# OSSILEDController2132.net
KiCad netlist of a schematic drawn in EAGLE
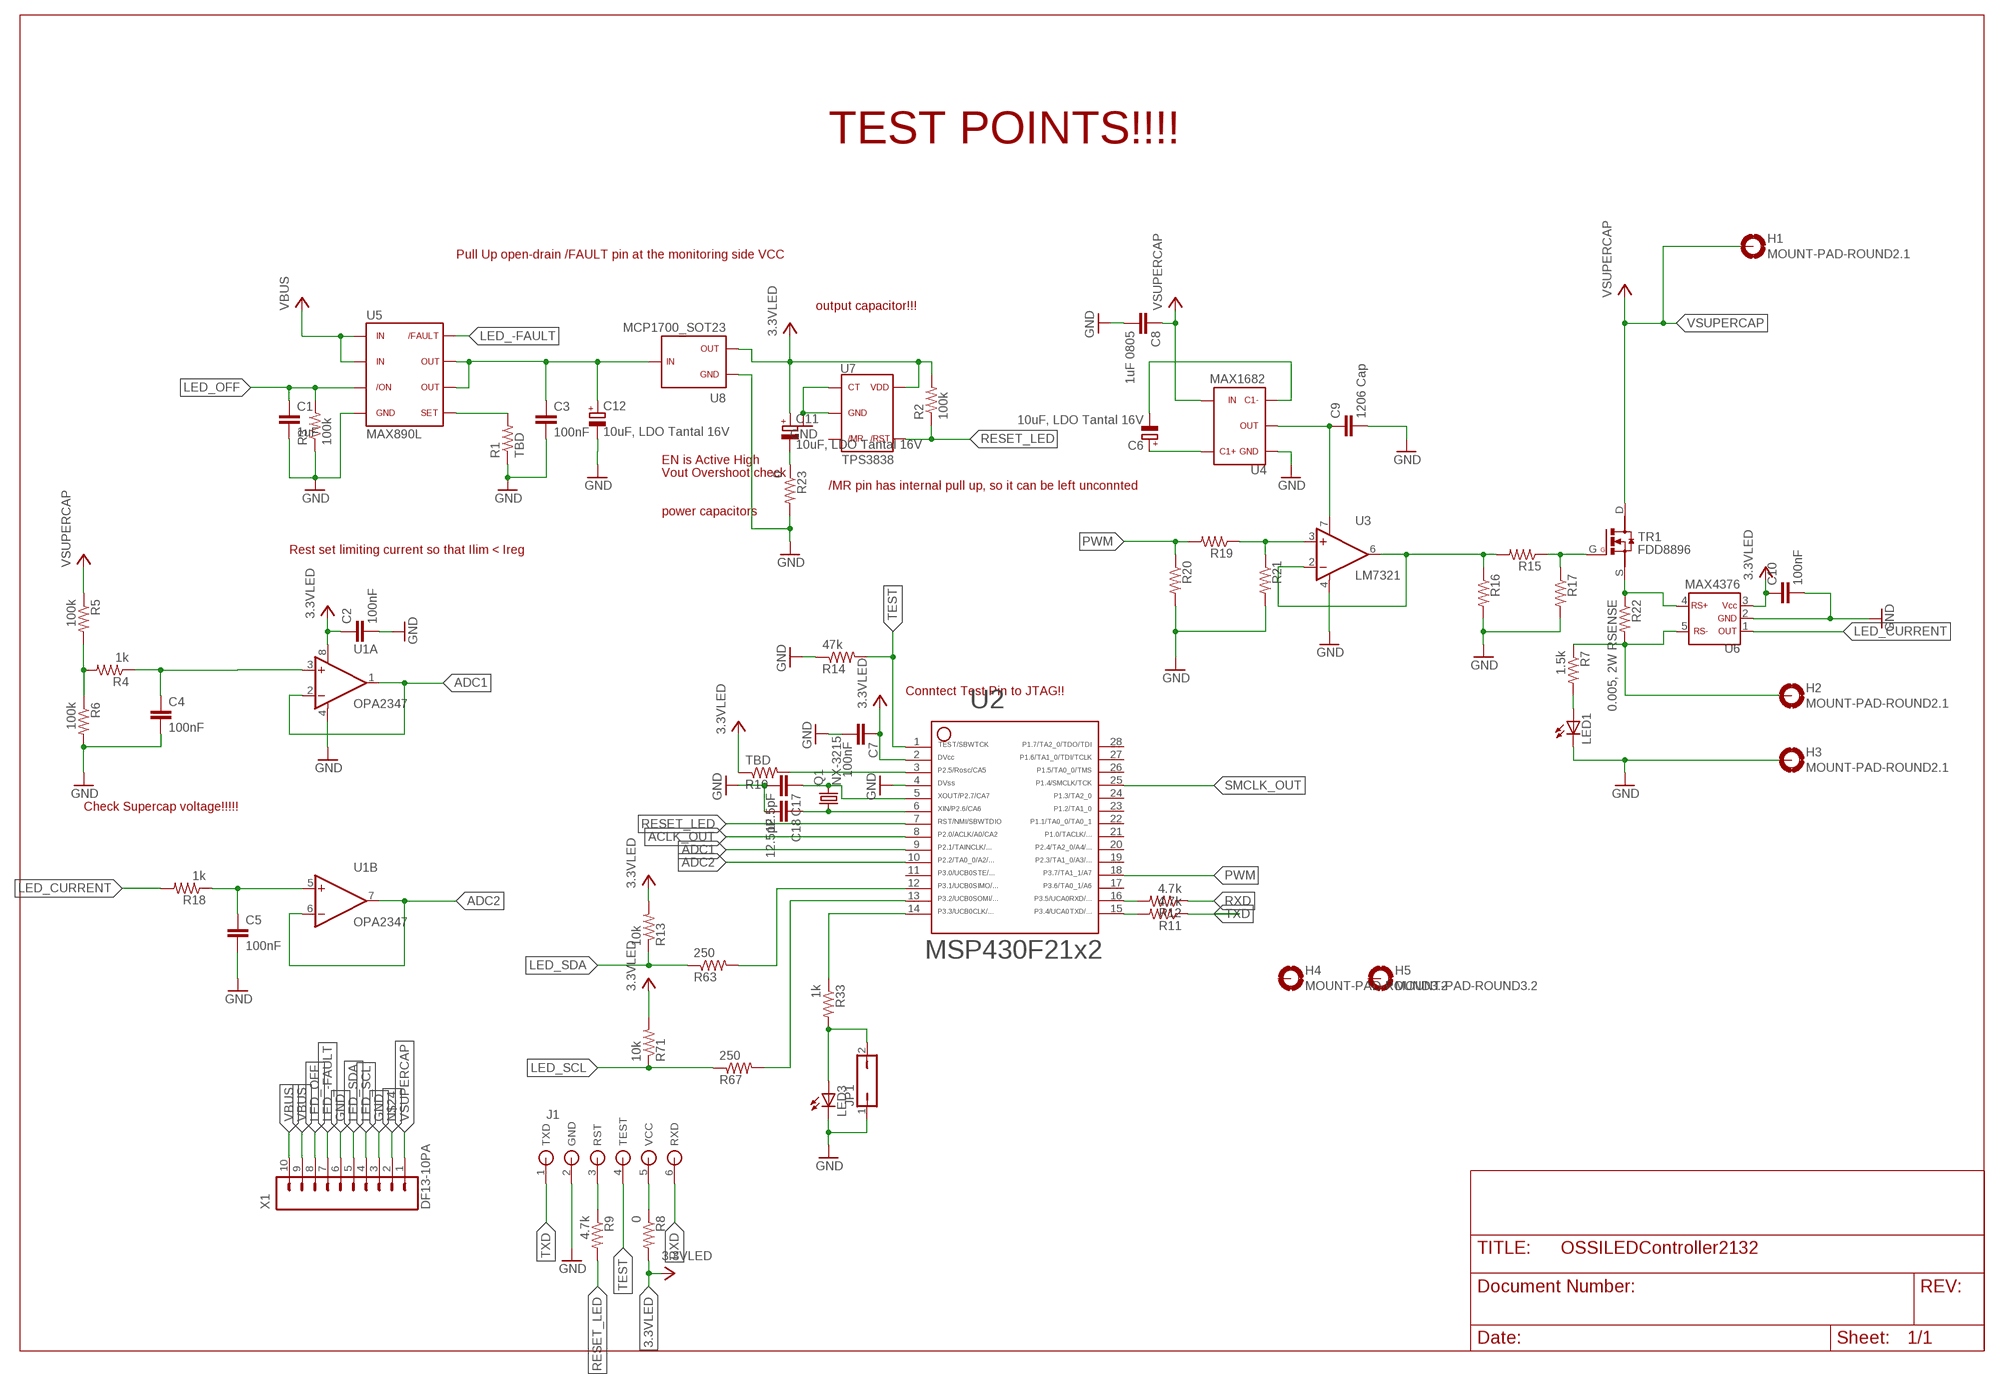
[diagram p0: schematic, sheet 1]

(export (version "E")
  (design (tool "Eeschema 10.0.6"))
  (components
    (comp (ref "C1")
      (value "1uF")
      (footprint "eagle-import:C0603(1608)")
      (libsource (lib "eagle-import") (part "C0603(1608)"))
    )
    (comp (ref "C2")
      (value "100nF")
      (footprint "eagle-import:C0603(1608)")
      (libsource (lib "eagle-import") (part "C0603(1608)"))
    )
    (comp (ref "C3")
      (value "100nF")
      (footprint "eagle-import:C0603(1608)")
      (libsource (lib "eagle-import") (part "C0603(1608)"))
    )
    (comp (ref "C4")
      (value "100nF")
      (footprint "eagle-import:C0603(1608)")
      (libsource (lib "eagle-import") (part "C0603(1608)"))
    )
    (comp (ref "C5")
      (value "100nF")
      (footprint "eagle-import:C0603(1608)")
      (libsource (lib "eagle-import") (part "C0603(1608)"))
    )
    (comp (ref "C6")
      (value "10uF, LDO Tantal 16V")
      (footprint "eagle-import:C1206(3216)-A")
      (libsource (lib "eagle-import") (part "C-TANTAL-A"))
    )
    (comp (ref "C7")
      (value "100nF")
      (footprint "eagle-import:C0603(1608)")
      (libsource (lib "eagle-import") (part "C0603(1608)"))
    )
    (comp (ref "C8")
      (value "1uF 0805")
      (footprint "eagle-import:C0805(2012)")
      (libsource (lib "eagle-import") (part "C0805(2012)"))
    )
    (comp (ref "C9")
      (value "1206 Cap")
      (footprint "eagle-import:C1206-GCM31")
      (libsource (lib "eagle-import") (part "C1206(3216)-GCM31"))
    )
    (comp (ref "C10")
      (value "100nF")
      (footprint "eagle-import:C0603(1608)")
      (libsource (lib "eagle-import") (part "C0603(1608)"))
    )
    (comp (ref "C11")
      (value "10uF, LDO Tantal 16V")
      (footprint "eagle-import:C1206(3216)-A")
      (libsource (lib "eagle-import") (part "C-TANTAL-A"))
    )
    (comp (ref "C12")
      (value "10uF, LDO Tantal 16V")
      (footprint "eagle-import:C1206(3216)-A")
      (libsource (lib "eagle-import") (part "C-TANTAL-A"))
    )
    (comp (ref "C17")
      (value "12.5pF")
      (footprint "eagle-import:C0603(1608)")
      (libsource (lib "eagle-import") (part "C0603(1608)"))
    )
    (comp (ref "C18")
      (value "12.5pF")
      (footprint "eagle-import:C0603(1608)")
      (libsource (lib "eagle-import") (part "C0603(1608)"))
    )
    (comp (ref "H1")
      (value "MOUNT-PAD-ROUND2.1")
      (footprint "eagle-import:2.1-PAD-ROUND")
      (libsource (lib "eagle-import") (part "MOUNT-PAD-ROUND2.1"))
    )
    (comp (ref "H2")
      (value "MOUNT-PAD-ROUND2.1")
      (footprint "eagle-import:2.1-PAD-ROUND")
      (libsource (lib "eagle-import") (part "MOUNT-PAD-ROUND2.1"))
    )
    (comp (ref "H3")
      (value "MOUNT-PAD-ROUND2.1")
      (footprint "eagle-import:2.1-PAD-ROUND")
      (libsource (lib "eagle-import") (part "MOUNT-PAD-ROUND2.1"))
    )
    (comp (ref "H4")
      (value "MOUNT-PAD-ROUND3.2")
      (footprint "eagle-import:3.2-PAD-ROUND")
      (libsource (lib "eagle-import") (part "MOUNT-PAD-ROUND3.2"))
    )
    (comp (ref "H5")
      (value "MOUNT-PAD-ROUND3.2")
      (footprint "eagle-import:3.2-PAD-ROUND")
      (libsource (lib "eagle-import") (part "MOUNT-PAD-ROUND3.2"))
    )
    (comp (ref "J1")
      (value "JTAG-SBW-6")
      (footprint "eagle-import:SMD-PAD-6")
      (libsource (lib "eagle-import") (part "JTAG-SBW-6"))
    )
    (comp (ref "JP1")
      (value "JP1Q")
      (footprint "eagle-import:JP1")
      (libsource (lib "eagle-import") (part "JP1Q"))
    )
    (comp (ref "LED1")
      (value "LEDCHIPLED_0603")
      (footprint "eagle-import:CHIPLED_0603")
      (libsource (lib "eagle-import") (part "LEDCHIPLED_0603"))
    )
    (comp (ref "LED3")
      (value "LED0603")
      (footprint "eagle-import:LED-0603")
      (libsource (lib "eagle-import") (part "LED0603"))
    )
    (comp (ref "Q1")
      (value "NX-3215")
      (footprint "eagle-import:NX-3215")
      (libsource (lib "eagle-import") (part "NX-3215"))
    )
    (comp (ref "R1")
      (value "TBD")
      (footprint "eagle-import:R0603(1608)")
      (libsource (lib "eagle-import") (part "R0603(1608)"))
    )
    (comp (ref "R2")
      (value "100k")
      (footprint "eagle-import:R0603(1608)")
      (libsource (lib "eagle-import") (part "R0603(1608)"))
    )
    (comp (ref "R3")
      (value "100k")
      (footprint "eagle-import:R0603(1608)")
      (libsource (lib "eagle-import") (part "R0603(1608)"))
    )
    (comp (ref "R4")
      (value "1k")
      (footprint "eagle-import:R0603(1608)")
      (libsource (lib "eagle-import") (part "R0603(1608)"))
    )
    (comp (ref "R5")
      (value "100k")
      (footprint "eagle-import:R0603(1608)")
      (libsource (lib "eagle-import") (part "R0603(1608)"))
    )
    (comp (ref "R6")
      (value "100k")
      (footprint "eagle-import:R0603(1608)")
      (libsource (lib "eagle-import") (part "R0603(1608)"))
    )
    (comp (ref "R7")
      (value "1.5k")
      (footprint "eagle-import:R0603(1608)")
      (libsource (lib "eagle-import") (part "R0603(1608)"))
    )
    (comp (ref "R8")
      (value "0")
      (footprint "eagle-import:R0603(1608)")
      (libsource (lib "eagle-import") (part "R0603(1608)"))
    )
    (comp (ref "R9")
      (value "4.7k")
      (footprint "eagle-import:R0603(1608)")
      (libsource (lib "eagle-import") (part "R0603(1608)"))
    )
    (comp (ref "R10")
      (value "TBD")
      (footprint "eagle-import:R0603(1608)")
      (libsource (lib "eagle-import") (part "R0603(1608)"))
    )
    (comp (ref "R11")
      (value "4.7k")
      (footprint "eagle-import:R0603(1608)")
      (libsource (lib "eagle-import") (part "R0603(1608)"))
    )
    (comp (ref "R12")
      (value "4.7k")
      (footprint "eagle-import:R0603(1608)")
      (libsource (lib "eagle-import") (part "R0603(1608)"))
    )
    (comp (ref "R13")
      (value "10k")
      (footprint "eagle-import:R0603(1608)")
      (libsource (lib "eagle-import") (part "R0603(1608)"))
    )
    (comp (ref "R14")
      (value "47k")
      (footprint "eagle-import:R0603(1608)")
      (libsource (lib "eagle-import") (part "R0603(1608)"))
    )
    (comp (ref "R15")
      (value "R0603(1608)")
      (footprint "eagle-import:R0603(1608)")
      (libsource (lib "eagle-import") (part "R0603(1608)"))
    )
    (comp (ref "R16")
      (value "R0603(1608)")
      (footprint "eagle-import:R0603(1608)")
      (libsource (lib "eagle-import") (part "R0603(1608)"))
    )
    (comp (ref "R17")
      (value "R0603(1608)")
      (footprint "eagle-import:R0603(1608)")
      (libsource (lib "eagle-import") (part "R0603(1608)"))
    )
    (comp (ref "R18")
      (value "1k")
      (footprint "eagle-import:R0603(1608)")
      (libsource (lib "eagle-import") (part "R0603(1608)"))
    )
    (comp (ref "R19")
      (value "R0603(1608)")
      (footprint "eagle-import:R0603(1608)")
      (libsource (lib "eagle-import") (part "R0603(1608)"))
    )
    (comp (ref "R20")
      (value "R0603(1608)")
      (footprint "eagle-import:R0603(1608)")
      (libsource (lib "eagle-import") (part "R0603(1608)"))
    )
    (comp (ref "R21")
      (value "R0603(1608)")
      (footprint "eagle-import:R0603(1608)")
      (libsource (lib "eagle-import") (part "R0603(1608)"))
    )
    (comp (ref "R22")
      (value "0.005, 2W RSENSE")
      (footprint "eagle-import:R4527(12070)")
      (libsource (lib "eagle-import") (part "RWSR2"))
    )
    (comp (ref "R23")
      (value "0")
      (footprint "eagle-import:R0603(1608)")
      (libsource (lib "eagle-import") (part "R0603(1608)"))
    )
    (comp (ref "R33")
      (value "1k")
      (footprint "eagle-import:R0603(1608)")
      (libsource (lib "eagle-import") (part "R0603(1608)"))
    )
    (comp (ref "R63")
      (value "250")
      (footprint "eagle-import:R0603(1608)")
      (libsource (lib "eagle-import") (part "R0603(1608)"))
    )
    (comp (ref "R67")
      (value "250")
      (footprint "eagle-import:R0603(1608)")
      (libsource (lib "eagle-import") (part "R0603(1608)"))
    )
    (comp (ref "R71")
      (value "10k")
      (footprint "eagle-import:R0603(1608)")
      (libsource (lib "eagle-import") (part "R0603(1608)"))
    )
    (comp (ref "TR1")
      (value "FDD8896")
      (footprint "eagle-import:TO252")
      (libsource (lib "eagle-import") (part "FDD8896"))
    )
    (comp (ref "U1")
      (value "OPA2347")
      (footprint "eagle-import:SOT23-8DCN")
      (libsource (lib "eagle-import") (part "OPA2347"))
    )
    (comp (ref "U2")
      (value "MSP430F2132")
      (footprint "eagle-import:PW28")
      (libsource (lib "eagle-import") (part "MSP430F2132"))
    )
    (comp (ref "U3")
      (value "LM7321")
      (footprint "eagle-import:SO8")
      (libsource (lib "eagle-import") (part "LM7321"))
    )
    (comp (ref "U4")
      (value "MAX1682")
      (footprint "eagle-import:SOT23-5DBV")
      (libsource (lib "eagle-import") (part "MAX1682"))
    )
    (comp (ref "U5")
      (value "MAX890L")
      (footprint "eagle-import:SO8")
      (libsource (lib "eagle-import") (part "MAX890L"))
    )
    (comp (ref "U6")
      (value "MAX4376")
      (footprint "eagle-import:SOT23-5DBV")
      (libsource (lib "eagle-import") (part "MAX4376"))
    )
    (comp (ref "U7")
      (value "TPS3838")
      (footprint "eagle-import:SOT23-5DBV")
      (libsource (lib "eagle-import") (part "TPS3838"))
    )
    (comp (ref "U8")
      (value "MCP1700_SOT23")
      (footprint "eagle-import:SOT23")
      (libsource (lib "eagle-import") (part "MCP1700_SOT23"))
    )
    (comp (ref "X1")
      (value "DF13-10PA")
      (footprint "eagle-import:DF13A-10P")
      (libsource (lib "eagle-import") (part "DF13-10PA"))
    )
  )
  (nets
    (net (code "1") (name "3.3VLED") (class "Default")
      (node (ref "C10") (pin "1") (pinfunction "1_1") (pintype "passive"))
      (node (ref "C11") (pin "1") (pinfunction "+_1") (pintype "passive"))
      (node (ref "C2") (pin "1") (pinfunction "1_1") (pintype "passive"))
      (node (ref "C7") (pin "1") (pinfunction "1_1") (pintype "passive"))
      (node (ref "R10") (pin "1") (pinfunction "1_1") (pintype "passive"))
      (node (ref "R13") (pin "2") (pinfunction "2_2") (pintype "passive"))
      (node (ref "R2") (pin "2") (pinfunction "2_2") (pintype "passive"))
      (node (ref "R71") (pin "2") (pinfunction "2_2") (pintype "passive"))
      (node (ref "R8") (pin "2") (pinfunction "2_2") (pintype "passive"))
      (node (ref "U1") (pin "8") (pinfunction "V+_8") (pintype "power_in"))
      (node (ref "U2") (pin "2") (pinfunction "2_2") (pintype "power_in"))
      (node (ref "U6") (pin "3") (pinfunction "P$3_3") (pintype "power_in"))
      (node (ref "U7") (pin "5") (pinfunction "P$5_5") (pintype "power_in"))
      (node (ref "U8") (pin "2") (pinfunction "2_2") (pintype "power_in"))
    )
    (net (code "2") (name "ACLK_OUT") (class "Default")
      (node (ref "U2") (pin "8") (pinfunction "8_8") (pintype "bidirectional"))
    )
    (net (code "3") (name "ADC1") (class "Default")
      (node (ref "U1") (pin "1") (pinfunction "OUT_1") (pintype "output"))
      (node (ref "U1") (pin "2") (pinfunction "-IN_2") (pintype "input"))
      (node (ref "U2") (pin "9") (pinfunction "9_9") (pintype "bidirectional"))
    )
    (net (code "4") (name "ADC2") (class "Default")
      (node (ref "U1") (pin "6") (pinfunction "-IN_6") (pintype "input"))
      (node (ref "U1") (pin "7") (pinfunction "OUT_7") (pintype "output"))
      (node (ref "U2") (pin "10") (pinfunction "10_10") (pintype "bidirectional"))
    )
    (net (code "5") (name "GND") (class "Default")
      (node (ref "C1") (pin "2") (pinfunction "2_2") (pintype "passive"))
      (node (ref "C10") (pin "2") (pinfunction "2_2") (pintype "passive"))
      (node (ref "C12") (pin "2") (pinfunction "-_2") (pintype "passive"))
      (node (ref "C17") (pin "2") (pinfunction "2_2") (pintype "passive"))
      (node (ref "C18") (pin "2") (pinfunction "2_2") (pintype "passive"))
      (node (ref "C2") (pin "2") (pinfunction "2_2") (pintype "passive"))
      (node (ref "C3") (pin "2") (pinfunction "2_2") (pintype "passive"))
      (node (ref "C4") (pin "2") (pinfunction "2_2") (pintype "passive"))
      (node (ref "C5") (pin "2") (pinfunction "2_2") (pintype "passive"))
      (node (ref "C7") (pin "2") (pinfunction "2_2") (pintype "passive"))
      (node (ref "C8") (pin "2") (pinfunction "2_2") (pintype "passive"))
      (node (ref "C9") (pin "P$2") (pinfunction "2_P$2") (pintype "passive"))
      (node (ref "H3") (pin "B3,2") (pinfunction "MOUNT_B3,2") (pintype "passive"))
      (node (ref "J1") (pin "2") (pinfunction "GND_2") (pintype "bidirectional"))
      (node (ref "JP1") (pin "1") (pinfunction "1_1") (pintype "passive"))
      (node (ref "LED1") (pin "C") (pinfunction "C_C") (pintype "passive"))
      (node (ref "LED3") (pin "C") (pinfunction "C_C") (pintype "passive"))
      (node (ref "R1") (pin "1") (pinfunction "1_1") (pintype "passive"))
      (node (ref "R14") (pin "1") (pinfunction "1_1") (pintype "passive"))
      (node (ref "R16") (pin "2") (pinfunction "2_2") (pintype "passive"))
      (node (ref "R17") (pin "2") (pinfunction "2_2") (pintype "passive"))
      (node (ref "R20") (pin "2") (pinfunction "2_2") (pintype "passive"))
      (node (ref "R21") (pin "2") (pinfunction "2_2") (pintype "passive"))
      (node (ref "R23") (pin "2") (pinfunction "2_2") (pintype "passive"))
      (node (ref "R3") (pin "1") (pinfunction "1_1") (pintype "passive"))
      (node (ref "R6") (pin "2") (pinfunction "2_2") (pintype "passive"))
      (node (ref "U1") (pin "4") (pinfunction "V-_4") (pintype "power_in"))
      (node (ref "U2") (pin "4") (pinfunction "4_4") (pintype "power_in"))
      (node (ref "U3") (pin "4") (pinfunction "V-_4") (pintype "power_in"))
      (node (ref "U4") (pin "1") (pinfunction "P$1_1") (pintype "power_in"))
      (node (ref "U5") (pin "4") (pinfunction "P$4_4") (pintype "power_in"))
      (node (ref "U6") (pin "2") (pinfunction "P$2_2") (pintype "power_in"))
      (node (ref "U7") (pin "1") (pinfunction "P$1_1") (pintype "bidirectional"))
      (node (ref "U7") (pin "2") (pinfunction "P$2_2") (pintype "power_in"))
      (node (ref "U8") (pin "1") (pinfunction "1_1") (pintype "power_in"))
      (node (ref "X1") (pin "3") (pinfunction "3_3") (pintype "passive"))
      (node (ref "X1") (pin "6") (pinfunction "6_6") (pintype "passive"))
    )
    (net (code "6") (name "LED_-FAULT") (class "Default")
      (node (ref "U5") (pin "8") (pinfunction "P$8_8") (pintype "output"))
      (node (ref "X1") (pin "7") (pinfunction "7_7") (pintype "passive"))
    )
    (net (code "7") (name "LED_CURRENT") (class "Default")
      (node (ref "R18") (pin "2") (pinfunction "2_2") (pintype "passive"))
      (node (ref "U6") (pin "1") (pinfunction "P$1_1") (pintype "output"))
    )
    (net (code "8") (name "LED_OFF") (class "Default")
      (node (ref "C1") (pin "1") (pinfunction "1_1") (pintype "passive"))
      (node (ref "R3") (pin "2") (pinfunction "2_2") (pintype "passive"))
      (node (ref "U5") (pin "3") (pinfunction "P$3_3") (pintype "input"))
      (node (ref "X1") (pin "8") (pinfunction "8_8") (pintype "passive"))
    )
    (net (code "9") (name "LED_SCL") (class "Default")
      (node (ref "R67") (pin "1") (pinfunction "1_1") (pintype "passive"))
      (node (ref "R71") (pin "1") (pinfunction "1_1") (pintype "passive"))
      (node (ref "X1") (pin "4") (pinfunction "4_4") (pintype "passive"))
    )
    (net (code "10") (name "LED_SDA") (class "Default")
      (node (ref "R13") (pin "1") (pinfunction "1_1") (pintype "passive"))
      (node (ref "R63") (pin "1") (pinfunction "1_1") (pintype "passive"))
      (node (ref "X1") (pin "5") (pinfunction "5_5") (pintype "passive"))
    )
    (net (code "11") (name "N$24") (class "Default")
      (node (ref "X1") (pin "2") (pinfunction "2_2") (pintype "passive"))
    )
    (net (code "12") (name "Net-(C6-+)") (class "Default")
      (node (ref "C6") (pin "1") (pinfunction "+_1") (pintype "passive"))
      (node (ref "U4") (pin "5") (pinfunction "P$5_5") (pintype "passive"))
    )
    (net (code "13") (name "Net-(C6--)") (class "Default")
      (node (ref "C6") (pin "2") (pinfunction "-_2") (pintype "passive"))
      (node (ref "U4") (pin "3") (pinfunction "P$3_3") (pintype "passive"))
    )
    (net (code "14") (name "Net-(C9-1)") (class "Default")
      (node (ref "C9") (pin "P$1") (pinfunction "1_P$1") (pintype "passive"))
      (node (ref "U3") (pin "7") (pinfunction "V+_7") (pintype "power_in"))
      (node (ref "U4") (pin "2") (pinfunction "P$2_2") (pintype "power_in"))
    )
    (net (code "15") (name "Net-(C11--)") (class "Default")
      (node (ref "C11") (pin "2") (pinfunction "-_2") (pintype "passive"))
      (node (ref "R23") (pin "1") (pinfunction "1_1") (pintype "passive"))
    )
    (net (code "16") (name "Net-(C12-+)") (class "Default")
      (node (ref "C12") (pin "1") (pinfunction "+_1") (pintype "passive"))
      (node (ref "C3") (pin "1") (pinfunction "1_1") (pintype "passive"))
      (node (ref "U5") (pin "6") (pinfunction "P$6_6") (pintype "output"))
      (node (ref "U5") (pin "7") (pinfunction "P$7_7") (pintype "output"))
      (node (ref "U8") (pin "3") (pinfunction "3_3") (pintype "power_in"))
    )
    (net (code "17") (name "Net-(C17-Pad1)") (class "Default")
      (node (ref "C17") (pin "1") (pinfunction "1_1") (pintype "passive"))
      (node (ref "Q1") (pin "2") (pinfunction "2_2") (pintype "passive"))
      (node (ref "U2") (pin "5") (pinfunction "5_5") (pintype "bidirectional"))
    )
    (net (code "18") (name "Net-(C18-Pad1)") (class "Default")
      (node (ref "C18") (pin "1") (pinfunction "1_1") (pintype "passive"))
      (node (ref "Q1") (pin "1") (pinfunction "1_1") (pintype "passive"))
      (node (ref "U2") (pin "6") (pinfunction "6_6") (pintype "bidirectional"))
    )
    (net (code "19") (name "Net-(H2-MOUNT)") (class "Default")
      (node (ref "H2") (pin "B3,2") (pinfunction "MOUNT_B3,2") (pintype "passive"))
      (node (ref "R22") (pin "P$2") (pinfunction "2_P$2") (pintype "passive"))
      (node (ref "R7") (pin "1") (pinfunction "1_1") (pintype "passive"))
      (node (ref "U6") (pin "5") (pinfunction "P$5_5") (pintype "input"))
    )
    (net (code "20") (name "Net-(J1-RST)") (class "Default")
      (node (ref "J1") (pin "3") (pinfunction "RST_3") (pintype "bidirectional"))
      (node (ref "R9") (pin "1") (pinfunction "1_1") (pintype "passive"))
    )
    (net (code "21") (name "Net-(J1-VCC)") (class "Default")
      (node (ref "J1") (pin "5") (pinfunction "VCC_5") (pintype "bidirectional"))
      (node (ref "R8") (pin "1") (pinfunction "1_1") (pintype "passive"))
    )
    (net (code "22") (name "Net-(JP1-Pad2)") (class "Default")
      (node (ref "JP1") (pin "2") (pinfunction "2_2") (pintype "passive"))
      (node (ref "LED3") (pin "A") (pinfunction "A_A") (pintype "passive"))
      (node (ref "R33") (pin "2") (pinfunction "2_2") (pintype "passive"))
    )
    (net (code "23") (name "Net-(LED1-PadA)") (class "Default")
      (node (ref "LED1") (pin "A") (pinfunction "A_A") (pintype "passive"))
      (node (ref "R7") (pin "2") (pinfunction "2_2") (pintype "passive"))
    )
    (net (code "24") (name "Net-(R4-Pad2)") (class "Default")
      (node (ref "R4") (pin "2") (pinfunction "2_2") (pintype "passive"))
      (node (ref "R5") (pin "2") (pinfunction "2_2") (pintype "passive"))
      (node (ref "R6") (pin "1") (pinfunction "1_1") (pintype "passive"))
    )
    (net (code "25") (name "Net-(R10-Pad2)") (class "Default")
      (node (ref "R10") (pin "2") (pinfunction "2_2") (pintype "passive"))
      (node (ref "U2") (pin "3") (pinfunction "3_3") (pintype "bidirectional"))
    )
    (net (code "26") (name "Net-(R11-Pad2)") (class "Default")
      (node (ref "R11") (pin "2") (pinfunction "2_2") (pintype "passive"))
      (node (ref "U2") (pin "15") (pinfunction "15_15") (pintype "bidirectional"))
    )
    (net (code "27") (name "Net-(R12-Pad2)") (class "Default")
      (node (ref "R12") (pin "2") (pinfunction "2_2") (pintype "passive"))
      (node (ref "U2") (pin "16") (pinfunction "16_16") (pintype "bidirectional"))
    )
    (net (code "28") (name "Net-(R15-Pad1)") (class "Default")
      (node (ref "R15") (pin "1") (pinfunction "1_1") (pintype "passive"))
      (node (ref "R17") (pin "1") (pinfunction "1_1") (pintype "passive"))
      (node (ref "TR1") (pin "G") (pinfunction "G_G") (pintype "bidirectional"))
    )
    (net (code "29") (name "Net-(R22-1)") (class "Default")
      (node (ref "R22") (pin "P$1") (pinfunction "1_P$1") (pintype "passive"))
      (node (ref "TR1") (pin "S") (pinfunction "S_S") (pintype "bidirectional"))
      (node (ref "U6") (pin "4") (pinfunction "P$4_4") (pintype "input"))
    )
    (net (code "30") (name "Net-(R33-Pad1)") (class "Default")
      (node (ref "R33") (pin "1") (pinfunction "1_1") (pintype "passive"))
      (node (ref "U2") (pin "14") (pinfunction "14_14") (pintype "bidirectional"))
    )
    (net (code "31") (name "Net-(R63-Pad2)") (class "Default")
      (node (ref "R63") (pin "2") (pinfunction "2_2") (pintype "passive"))
      (node (ref "U2") (pin "12") (pinfunction "12_12") (pintype "bidirectional"))
    )
    (net (code "32") (name "Net-(R67-Pad2)") (class "Default")
      (node (ref "R67") (pin "2") (pinfunction "2_2") (pintype "passive"))
      (node (ref "U2") (pin "13") (pinfunction "13_13") (pintype "bidirectional"))
    )
    (net (code "33") (name "Net-(U1A-+IN)") (class "Default")
      (node (ref "C4") (pin "1") (pinfunction "1_1") (pintype "passive"))
      (node (ref "R4") (pin "1") (pinfunction "1_1") (pintype "passive"))
      (node (ref "U1") (pin "3") (pinfunction "+IN_3") (pintype "input"))
    )
    (net (code "34") (name "Net-(U1B-+IN)") (class "Default")
      (node (ref "C5") (pin "1") (pinfunction "1_1") (pintype "passive"))
      (node (ref "R18") (pin "1") (pinfunction "1_1") (pintype "passive"))
      (node (ref "U1") (pin "5") (pinfunction "+IN_5") (pintype "input"))
    )
    (net (code "35") (name "Net-(U3-+IN)") (class "Default")
      (node (ref "R19") (pin "1") (pinfunction "1_1") (pintype "passive"))
      (node (ref "R21") (pin "1") (pinfunction "1_1") (pintype "passive"))
      (node (ref "U3") (pin "3") (pinfunction "+IN_3") (pintype "input"))
    )
    (net (code "36") (name "Net-(U3--IN)") (class "Default")
      (node (ref "R15") (pin "2") (pinfunction "2_2") (pintype "passive"))
      (node (ref "R16") (pin "1") (pinfunction "1_1") (pintype "passive"))
      (node (ref "U3") (pin "2") (pinfunction "-IN_2") (pintype "input"))
      (node (ref "U3") (pin "6") (pinfunction "OUT_6") (pintype "output"))
    )
    (net (code "37") (name "Net-(U5-P$5)") (class "Default")
      (node (ref "R1") (pin "2") (pinfunction "2_2") (pintype "passive"))
      (node (ref "U5") (pin "5") (pinfunction "P$5_5") (pintype "passive"))
    )
    (net (code "38") (name "PWM") (class "Default")
      (node (ref "R19") (pin "2") (pinfunction "2_2") (pintype "passive"))
      (node (ref "R20") (pin "1") (pinfunction "1_1") (pintype "passive"))
      (node (ref "U2") (pin "18") (pinfunction "18_18") (pintype "bidirectional"))
    )
    (net (code "39") (name "RESET_LED") (class "Default")
      (node (ref "R2") (pin "1") (pinfunction "1_1") (pintype "passive"))
      (node (ref "R9") (pin "2") (pinfunction "2_2") (pintype "passive"))
      (node (ref "U2") (pin "7") (pinfunction "7_7") (pintype "input"))
      (node (ref "U7") (pin "4") (pinfunction "P$4_4") (pintype "output"))
    )
    (net (code "40") (name "RXD") (class "Default")
      (node (ref "J1") (pin "6") (pinfunction "RXD_6") (pintype "bidirectional"))
      (node (ref "R12") (pin "1") (pinfunction "1_1") (pintype "passive"))
    )
    (net (code "41") (name "SMCLK_OUT") (class "Default")
      (node (ref "U2") (pin "25") (pinfunction "25_25") (pintype "bidirectional"))
    )
    (net (code "42") (name "TEST") (class "Default")
      (node (ref "J1") (pin "4") (pinfunction "TEST_4") (pintype "bidirectional"))
      (node (ref "R14") (pin "2") (pinfunction "2_2") (pintype "passive"))
      (node (ref "U2") (pin "1") (pinfunction "1_1") (pintype "input"))
    )
    (net (code "43") (name "TXD") (class "Default")
      (node (ref "J1") (pin "1") (pinfunction "TXD_1") (pintype "bidirectional"))
      (node (ref "R11") (pin "1") (pinfunction "1_1") (pintype "passive"))
    )
    (net (code "44") (name "VBUS") (class "Default")
      (node (ref "U5") (pin "1") (pinfunction "P$1_1") (pintype "input"))
      (node (ref "U5") (pin "2") (pinfunction "P$2_2") (pintype "input"))
      (node (ref "X1") (pin "10") (pinfunction "10_10") (pintype "passive"))
      (node (ref "X1") (pin "9") (pinfunction "9_9") (pintype "passive"))
    )
    (net (code "45") (name "VSUPERCAP") (class "Default")
      (node (ref "C8") (pin "1") (pinfunction "1_1") (pintype "passive"))
      (node (ref "H1") (pin "B3,2") (pinfunction "MOUNT_B3,2") (pintype "passive"))
      (node (ref "R5") (pin "1") (pinfunction "1_1") (pintype "passive"))
      (node (ref "TR1") (pin "D") (pinfunction "D_D") (pintype "bidirectional"))
      (node (ref "U4") (pin "4") (pinfunction "P$4_4") (pintype "power_in"))
      (node (ref "X1") (pin "1") (pinfunction "1_1") (pintype "passive"))
    )
    (net (code "46") (name "unconnected-(H4-MOUNT-PadB3,2)") (class "Default")
      (node (ref "H4") (pin "B3,2") (pinfunction "MOUNT_B3,2") (pintype "passive"))
    )
    (net (code "47") (name "unconnected-(H5-MOUNT-PadB3,2)") (class "Default")
      (node (ref "H5") (pin "B3,2") (pinfunction "MOUNT_B3,2") (pintype "passive"))
    )
    (net (code "48") (name "unconnected-(U2-Pad11)") (class "Default")
      (node (ref "U2") (pin "11") (pinfunction "11_11") (pintype "bidirectional"))
    )
    (net (code "49") (name "unconnected-(U2-Pad17)") (class "Default")
      (node (ref "U2") (pin "17") (pinfunction "17_17") (pintype "bidirectional"))
    )
    (net (code "50") (name "unconnected-(U2-Pad19)") (class "Default")
      (node (ref "U2") (pin "19") (pinfunction "19_19") (pintype "bidirectional"))
    )
    (net (code "51") (name "unconnected-(U2-Pad20)") (class "Default")
      (node (ref "U2") (pin "20") (pinfunction "20_20") (pintype "bidirectional"))
    )
    (net (code "52") (name "unconnected-(U2-Pad21)") (class "Default")
      (node (ref "U2") (pin "21") (pinfunction "21_21") (pintype "bidirectional"))
    )
    (net (code "53") (name "unconnected-(U2-Pad22)") (class "Default")
      (node (ref "U2") (pin "22") (pinfunction "22_22") (pintype "bidirectional"))
    )
    (net (code "54") (name "unconnected-(U2-Pad23)") (class "Default")
      (node (ref "U2") (pin "23") (pinfunction "23_23") (pintype "bidirectional"))
    )
    (net (code "55") (name "unconnected-(U2-Pad24)") (class "Default")
      (node (ref "U2") (pin "24") (pinfunction "24_24") (pintype "bidirectional"))
    )
    (net (code "56") (name "unconnected-(U2-Pad26)") (class "Default")
      (node (ref "U2") (pin "26") (pinfunction "26_26") (pintype "bidirectional"))
    )
    (net (code "57") (name "unconnected-(U2-Pad27)") (class "Default")
      (node (ref "U2") (pin "27") (pinfunction "27_27") (pintype "bidirectional"))
    )
    (net (code "58") (name "unconnected-(U2-Pad28)") (class "Default")
      (node (ref "U2") (pin "28") (pinfunction "28_28") (pintype "bidirectional"))
    )
    (net (code "59") (name "unconnected-(U7-P$3-Pad3)") (class "Default")
      (node (ref "U7") (pin "3") (pinfunction "P$3_3") (pintype "input"))
    )
  )
)
